# TK511_DC-PSU.net
KiCad netlist of a schematic drawn in Altium Designer
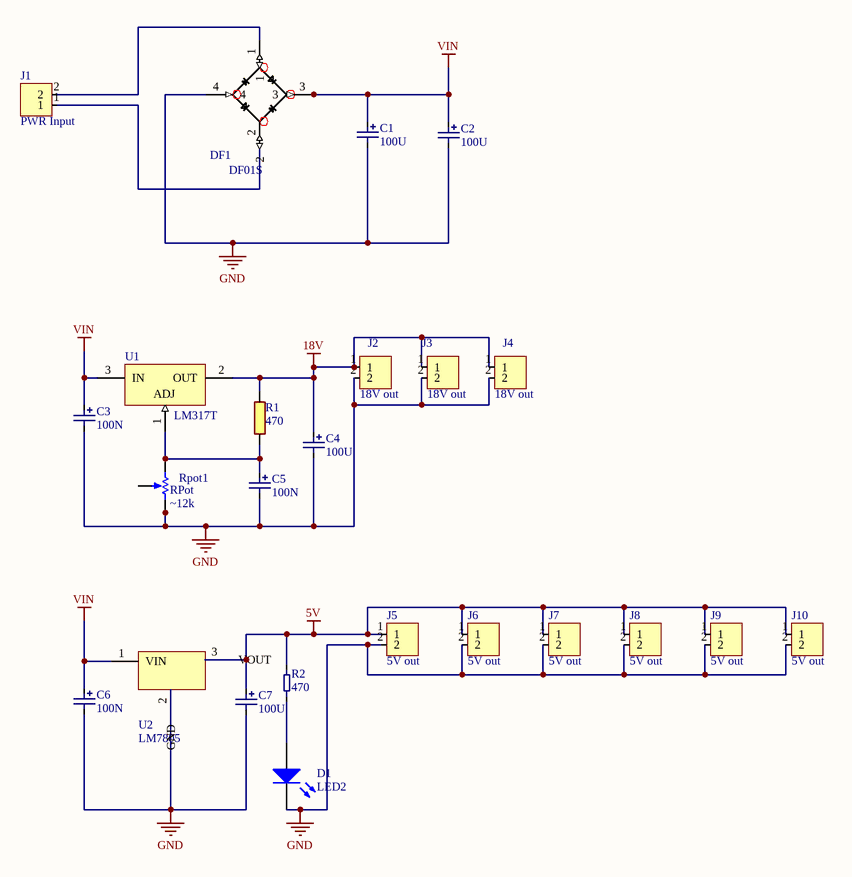
[diagram p0: TK511_DC-PSU.SchDoc]

(export (version "E")
  (design (tool "Eeschema 10.0.6"))
  (components
    (comp (ref "C1") (value "100U") (footprint "CAP 2.5mm") (libsource (lib "Schlib1") (part "CAP")))
    (comp (ref "C2") (value "100U") (footprint "CAP 2.5mm") (libsource (lib "Schlib1") (part "CAP")))
    (comp (ref "C3") (value "100N") (footprint "RAD-0.2") (libsource (lib "Schlib1") (part "CAP")))
    (comp (ref "C4") (value "100U") (footprint "CAP 2.5mm") (libsource (lib "Schlib1") (part "CAP")))
    (comp (ref "C5") (value "100N") (footprint "RAD-0.2") (libsource (lib "Schlib1") (part "CAP")))
    (comp (ref "C6") (value "100N") (footprint "RAD-0.2") (libsource (lib "Schlib1") (part "CAP")))
    (comp (ref "C7") (value "100U") (footprint "CAP 2.5mm") (libsource (lib "Schlib1") (part "CAP")))
    (comp (ref "D1")
      (value "LED2")
      (footprint "6-0805_L")
      (description "Typical RED, GREEN, YELLOW, AMBER GaAs LED")
      (fields (field (name "PUBLISHER") "Altium Limited"))
      (libsource (lib "Miscellaneous Devices") (part "LED2"))
    )
    (comp (ref "DF1")
      (value "DF01S")
      (footprint "DF01S_PCB")
      (description "Likeretterbro")
      (libsource (lib "DF01S") (part "DF01S"))
    )
    (comp (ref "J1") (value "PWR Input") (footprint "JST 2pin") (libsource (lib "") (part "JST 2pin_1")))
    (comp (ref "J2") (value "18V out") (footprint "JST 2pin") (libsource (lib "Schlib1") (part "JST 2pin")))
    (comp (ref "J3") (value "18V out") (footprint "JST 2pin") (libsource (lib "Schlib1") (part "JST 2pin")))
    (comp (ref "J4") (value "18V out") (footprint "JST 2pin") (libsource (lib "Schlib1") (part "JST 2pin")))
    (comp (ref "J5") (value "5V out") (footprint "JST 2pin") (libsource (lib "Schlib1") (part "JST 2pin")))
    (comp (ref "J6") (value "5V out") (footprint "JST 2pin") (libsource (lib "Schlib1") (part "JST 2pin")))
    (comp (ref "J7") (value "5V out") (footprint "JST 2pin") (libsource (lib "Schlib1") (part "JST 2pin")))
    (comp (ref "J8") (value "5V out") (footprint "JST 2pin") (libsource (lib "Schlib1") (part "JST 2pin")))
    (comp (ref "J9") (value "5V out") (footprint "JST 2pin") (libsource (lib "Schlib1") (part "JST 2pin")))
    (comp (ref "J10") (value "5V out") (footprint "JST 2pin") (libsource (lib "Schlib1") (part "JST 2pin")))
    (comp (ref "R1")
      (value "470")
      (footprint "RESA_0.25W")
      (description "0.25W 1% Generic resistor")
      (libsource (lib "OVLib") (part "Resistor2"))
    )
    (comp (ref "R2") (value "470") (footprint "6-0805_N") (libsource (lib "Schlib1") (part "R")))
    (comp (ref "Rpot1")
      (value "RPot")
      (footprint "VR5")
      (description "Potentiometer")
      (fields (field (name "ALTIUM_VALUE") "~12k") (field (name "PUBLISHER") "Altium Limited"))
      (libsource (lib "Miscellaneous Devices") (part "RPot"))
    )
    (comp (ref "U1")
      (value "LM317T")
      (footprint "221A-06")
      (description "Three-Terminal Adjustable Output Positive Voltage Regulator")
      (fields (field (name "PUBLISHER") "Altium Limited"))
      (libsource (lib "ON Semi Power Mgt Voltage Regulator") (part "LM317T"))
    )
    (comp (ref "U2") (value "LM7805") (footprint "221A-06") (libsource (lib "DF01S") (part "LM7805")))
  )
  (nets
    (net (code "1") (name "5V") (class "Default")
      (node (ref "C7") (pin "2") (pinfunction "2_2") (pintype "passive"))
      (node (ref "J10") (pin "1") (pinfunction "1_1") (pintype "passive"))
      (node (ref "J5") (pin "1") (pinfunction "1_1") (pintype "passive"))
      (node (ref "J6") (pin "1") (pinfunction "1_1") (pintype "passive"))
      (node (ref "J7") (pin "1") (pinfunction "1_1") (pintype "passive"))
      (node (ref "J8") (pin "1") (pinfunction "1_1") (pintype "passive"))
      (node (ref "J9") (pin "1") (pinfunction "1_1") (pintype "passive"))
      (node (ref "R2") (pin "2") (pinfunction "2_2") (pintype "passive"))
      (node (ref "U2") (pin "3") (pinfunction "VOUT_3") (pintype "power_in"))
    )
    (net (code "2") (name "18V") (class "Default")
      (node (ref "C4") (pin "2") (pinfunction "2_2") (pintype "passive"))
      (node (ref "J2") (pin "1") (pinfunction "1_1") (pintype "passive"))
      (node (ref "J3") (pin "1") (pinfunction "1_1") (pintype "passive"))
      (node (ref "J4") (pin "1") (pinfunction "1_1") (pintype "passive"))
      (node (ref "R1") (pin "2") (pinfunction "2_2") (pintype "passive"))
      (node (ref "U1") (pin "2") (pinfunction "OUT_2") (pintype "power_in"))
    )
    (net (code "3") (name "GND") (class "Default")
      (node (ref "C1") (pin "1") (pinfunction "1_1") (pintype "passive"))
      (node (ref "C2") (pin "1") (pinfunction "1_1") (pintype "passive"))
      (node (ref "C3") (pin "1") (pinfunction "1_1") (pintype "passive"))
      (node (ref "C4") (pin "1") (pinfunction "1_1") (pintype "passive"))
      (node (ref "C5") (pin "1") (pinfunction "1_1") (pintype "passive"))
      (node (ref "C6") (pin "1") (pinfunction "1_1") (pintype "passive"))
      (node (ref "C7") (pin "1") (pinfunction "1_1") (pintype "passive"))
      (node (ref "D1") (pin "2") (pinfunction "K_2") (pintype "passive"))
      (node (ref "DF1") (pin "4") (pinfunction "4_4") (pintype "input"))
      (node (ref "J10") (pin "2") (pinfunction "2_2") (pintype "passive"))
      (node (ref "J2") (pin "2") (pinfunction "2_2") (pintype "passive"))
      (node (ref "J3") (pin "2") (pinfunction "2_2") (pintype "passive"))
      (node (ref "J4") (pin "2") (pinfunction "2_2") (pintype "passive"))
      (node (ref "J5") (pin "2") (pinfunction "2_2") (pintype "passive"))
      (node (ref "J6") (pin "2") (pinfunction "2_2") (pintype "passive"))
      (node (ref "J7") (pin "2") (pinfunction "2_2") (pintype "passive"))
      (node (ref "J8") (pin "2") (pinfunction "2_2") (pintype "passive"))
      (node (ref "J9") (pin "2") (pinfunction "2_2") (pintype "passive"))
      (node (ref "Rpot1") (pin "2") (pinfunction "BOT_2") (pintype "passive"))
      (node (ref "U2") (pin "2") (pinfunction "GND_2") (pintype "power_in"))
    )
    (net (code "4") (name "Net-(D1-A)") (class "Default")
      (node (ref "D1") (pin "1") (pinfunction "A_1") (pintype "passive"))
      (node (ref "R2") (pin "1") (pinfunction "1_1") (pintype "passive"))
    )
    (net (code "5") (name "Net-(DF1-Pad1)") (class "Default")
      (node (ref "DF1") (pin "1") (pinfunction "1_1") (pintype "bidirectional"))
      (node (ref "J1") (pin "2") (pinfunction "2_2") (pintype "passive"))
    )
    (net (code "6") (name "Net-(DF1-Pad2)") (class "Default")
      (node (ref "DF1") (pin "2") (pinfunction "2_2") (pintype "bidirectional"))
      (node (ref "J1") (pin "1") (pinfunction "1_1") (pintype "passive"))
    )
    (net (code "7") (name "Net-(Rpot1-TOP)") (class "Default")
      (node (ref "C5") (pin "2") (pinfunction "2_2") (pintype "passive"))
      (node (ref "R1") (pin "1") (pinfunction "1_1") (pintype "passive"))
      (node (ref "Rpot1") (pin "1") (pinfunction "TOP_1") (pintype "passive"))
      (node (ref "U1") (pin "1") (pinfunction "ADJ_1") (pintype "input"))
    )
    (net (code "8") (name "VIN") (class "Default")
      (node (ref "C1") (pin "2") (pinfunction "2_2") (pintype "passive"))
      (node (ref "C2") (pin "2") (pinfunction "2_2") (pintype "passive"))
      (node (ref "C3") (pin "2") (pinfunction "2_2") (pintype "passive"))
      (node (ref "C6") (pin "2") (pinfunction "2_2") (pintype "passive"))
      (node (ref "DF1") (pin "3") (pinfunction "3_3") (pintype "output"))
      (node (ref "U1") (pin "3") (pinfunction "IN_3") (pintype "power_in"))
      (node (ref "U2") (pin "1") (pinfunction "VIN_1") (pintype "power_in"))
    )
    (net (code "9") (name "unconnected-(Rpot1-TAP-Pad3)") (class "Default")
      (node (ref "Rpot1") (pin "3") (pinfunction "TAP_3") (pintype "passive"))
    )
  )
)
